# Current_Sense.net
KiCad netlist of a schematic drawn in Altium Designer
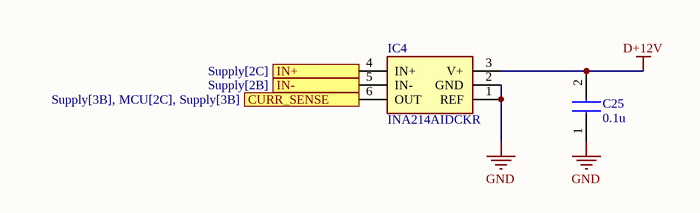
[diagram p0: Current_Sense.SchDoc]

(export (version "E")
  (design (tool "Eeschema 10.0.6"))
  (components
    (comp (ref "C25")
      (value "0.1u")
      (footprint "SamacSys:CAPC1608X90N")
      (description "CC0603KRX7R8BB104")
      (fields (field (name "MOUSER PART NUMBER") "603-CC603KRX7R8BB104"))
      (libsource (lib "*") (part "CC0603KRX7R8BB104"))
    )
    (comp (ref "IC4")
      (value "INA214AIDCKR")
      (footprint "SamacSys:SOT65P210X110-6N")
      (description "Integrated Circuit")
      (fields (field (name "MOUSER PART NUMBER") "595-INA214AIDCKR"))
      (libsource (lib "*") (part "INA214AIDCKR"))
    )
  )
  (nets
    (net (code "1") (name "/CURR_SENSE") (class "Default")
      (node (ref "IC4") (pin "6") (pinfunction "OUT_6") (pintype "passive"))
    )
    (net (code "2") (name "/IN+") (class "Default")
      (node (ref "IC4") (pin "4") (pinfunction "IN+_4") (pintype "passive"))
    )
    (net (code "3") (name "/IN-") (class "Default")
      (node (ref "IC4") (pin "5") (pinfunction "IN-_5") (pintype "passive"))
    )
    (net (code "4") (name "D+12V") (class "Default")
      (node (ref "C25") (pin "2") (pinfunction "2_2") (pintype "passive"))
      (node (ref "IC4") (pin "3") (pinfunction "V+_3") (pintype "passive"))
    )
    (net (code "5") (name "GND") (class "Default")
      (node (ref "C25") (pin "1") (pinfunction "1_1") (pintype "passive"))
      (node (ref "IC4") (pin "1") (pinfunction "REF_1") (pintype "passive"))
      (node (ref "IC4") (pin "2") (pinfunction "GND_2") (pintype "passive"))
    )
  )
)
